# alarm.net
KiCad netlist of a schematic drawn in EAGLE
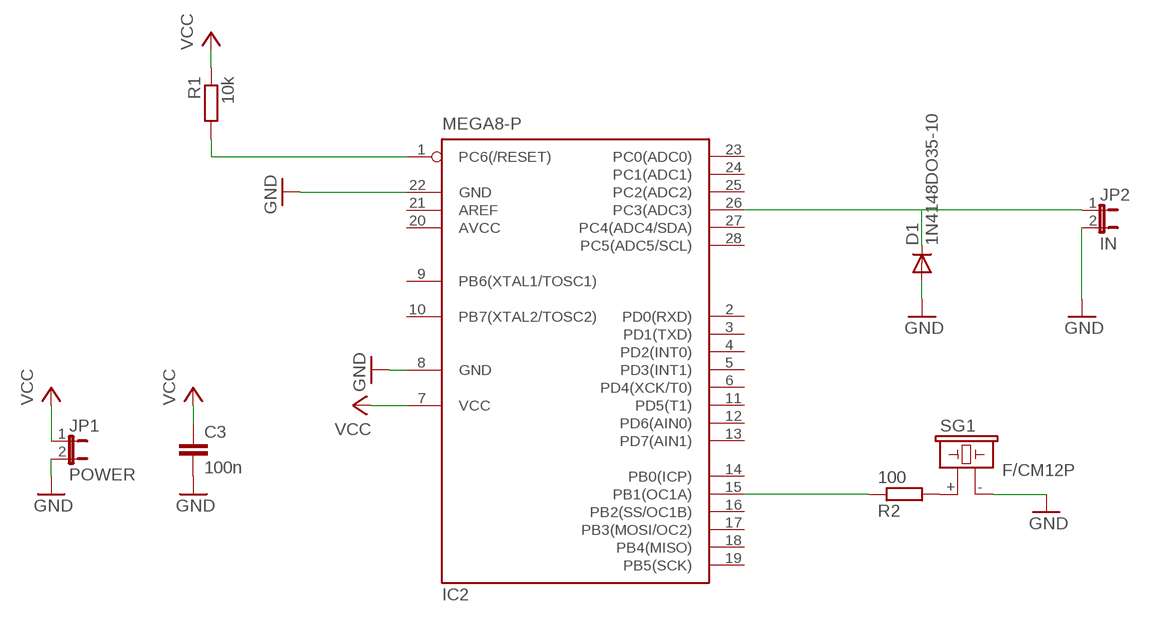
[diagram p0: schematic, sheet 1]

(export (version "E")
  (design (tool "Eeschema 10.0.6"))
  (components
    (comp (ref "C3")
      (value "100n")
      (footprint "eagle-import:C025-024X044")
      (libsource (lib "eagle-import") (part "C-EU025-024X044"))
    )
    (comp (ref "D1")
      (value "1N4148DO35-10")
      (footprint "eagle-import:DO35-10")
      (libsource (lib "eagle-import") (part "1N4148DO35-10"))
    )
    (comp (ref "IC2")
      (value "MEGA8-P")
      (footprint "eagle-import:DIL28-3")
      (libsource (lib "eagle-import") (part "MEGA8-P"))
    )
    (comp (ref "JP1")
      (value "POWER")
      (footprint "eagle-import:JP1")
      (libsource (lib "eagle-import") (part "JP1E"))
    )
    (comp (ref "JP2")
      (value "IN")
      (footprint "eagle-import:JP1")
      (libsource (lib "eagle-import") (part "JP1E"))
    )
    (comp (ref "R1")
      (value "10k")
      (footprint "eagle-import:0207_15")
      (libsource (lib "eagle-import") (part "R-EU_0207/15"))
    )
    (comp (ref "R2")
      (value "100")
      (footprint "eagle-import:0207_10")
      (libsource (lib "eagle-import") (part "R-EU_0207/10"))
    )
    (comp (ref "SG1")
      (value "F/CM12P")
      (footprint "eagle-import:F_CM12P")
      (libsource (lib "eagle-import") (part "F/CM12P"))
    )
  )
  (nets
    (net (code "1") (name "/AVCC") (class "Default")
      (node (ref "IC2") (pin "20") (pinfunction "AVCC_20") (pintype "power_in"))
    )
    (net (code "2") (name "GND") (class "Default")
      (node (ref "C3") (pin "2") (pinfunction "2_2") (pintype "passive"))
      (node (ref "D1") (pin "A") (pinfunction "A_A") (pintype "passive"))
      (node (ref "IC2") (pin "22") (pinfunction "GND_22") (pintype "power_in"))
      (node (ref "IC2") (pin "8") (pinfunction "GND_8") (pintype "power_in"))
      (node (ref "JP1") (pin "2") (pinfunction "2_2") (pintype "passive"))
      (node (ref "JP2") (pin "2") (pinfunction "2_2") (pintype "passive"))
      (node (ref "SG1") (pin "-") (pinfunction "2_-") (pintype "passive"))
    )
    (net (code "3") (name "Net-(IC2-PB1(OC1A))") (class "Default")
      (node (ref "IC2") (pin "15") (pinfunction "PB1(OC1A)_15") (pintype "bidirectional"))
      (node (ref "R2") (pin "1") (pinfunction "1_1") (pintype "passive"))
    )
    (net (code "4") (name "Net-(IC2-PC3(ADC3))") (class "Default")
      (node (ref "D1") (pin "C") (pinfunction "C_C") (pintype "passive"))
      (node (ref "IC2") (pin "26") (pinfunction "PC3(ADC3)_26") (pintype "bidirectional"))
      (node (ref "JP2") (pin "1") (pinfunction "1_1") (pintype "passive"))
    )
    (net (code "5") (name "Net-(IC2-PC6({slash}RESET))") (class "Default")
      (node (ref "IC2") (pin "1") (pinfunction "PC6(/RESET)_1") (pintype "bidirectional"))
      (node (ref "R1") (pin "2") (pinfunction "2_2") (pintype "passive"))
    )
    (net (code "6") (name "Net-(SG1-1)") (class "Default")
      (node (ref "R2") (pin "2") (pinfunction "2_2") (pintype "passive"))
      (node (ref "SG1") (pin "+") (pinfunction "1_+") (pintype "passive"))
    )
    (net (code "7") (name "VCC") (class "Default")
      (node (ref "C3") (pin "1") (pinfunction "1_1") (pintype "passive"))
      (node (ref "IC2") (pin "7") (pinfunction "VCC_7") (pintype "power_in"))
      (node (ref "JP1") (pin "1") (pinfunction "1_1") (pintype "passive"))
      (node (ref "R1") (pin "1") (pinfunction "1_1") (pintype "passive"))
    )
    (net (code "8") (name "unconnected-(IC2-AREF-Pad21)") (class "Default")
      (node (ref "IC2") (pin "21") (pinfunction "AREF_21") (pintype "passive"))
    )
    (net (code "9") (name "unconnected-(IC2-PB0(ICP)-Pad14)") (class "Default")
      (node (ref "IC2") (pin "14") (pinfunction "PB0(ICP)_14") (pintype "bidirectional"))
    )
    (net (code "10") (name "unconnected-(IC2-PB2(SS{slash}OC1B)-Pad16)") (class "Default")
      (node (ref "IC2") (pin "16") (pinfunction "PB2(SS/OC1B)_16") (pintype "bidirectional"))
    )
    (net (code "11") (name "unconnected-(IC2-PB3(MOSI{slash}OC2)-Pad17)") (class "Default")
      (node (ref "IC2") (pin "17") (pinfunction "PB3(MOSI/OC2)_17") (pintype "bidirectional"))
    )
    (net (code "12") (name "unconnected-(IC2-PB4(MISO)-Pad18)") (class "Default")
      (node (ref "IC2") (pin "18") (pinfunction "PB4(MISO)_18") (pintype "bidirectional"))
    )
    (net (code "13") (name "unconnected-(IC2-PB5(SCK)-Pad19)") (class "Default")
      (node (ref "IC2") (pin "19") (pinfunction "PB5(SCK)_19") (pintype "bidirectional"))
    )
    (net (code "14") (name "unconnected-(IC2-PB6(XTAL1{slash}TOSC1)-Pad9)") (class "Default")
      (node (ref "IC2") (pin "9") (pinfunction "PB6(XTAL1/TOSC1)_9") (pintype "bidirectional"))
    )
    (net (code "15") (name "unconnected-(IC2-PB7(XTAL2{slash}TOSC2)-Pad10)") (class "Default")
      (node (ref "IC2") (pin "10") (pinfunction "PB7(XTAL2/TOSC2)_10") (pintype "bidirectional"))
    )
    (net (code "16") (name "unconnected-(IC2-PC0(ADC0)-Pad23)") (class "Default")
      (node (ref "IC2") (pin "23") (pinfunction "PC0(ADC0)_23") (pintype "bidirectional"))
    )
    (net (code "17") (name "unconnected-(IC2-PC1(ADC1)-Pad24)") (class "Default")
      (node (ref "IC2") (pin "24") (pinfunction "PC1(ADC1)_24") (pintype "bidirectional"))
    )
    (net (code "18") (name "unconnected-(IC2-PC2(ADC2)-Pad25)") (class "Default")
      (node (ref "IC2") (pin "25") (pinfunction "PC2(ADC2)_25") (pintype "bidirectional"))
    )
    (net (code "19") (name "unconnected-(IC2-PC4(ADC4{slash}SDA)-Pad27)") (class "Default")
      (node (ref "IC2") (pin "27") (pinfunction "PC4(ADC4/SDA)_27") (pintype "bidirectional"))
    )
    (net (code "20") (name "unconnected-(IC2-PC5(ADC5{slash}SCL)-Pad28)") (class "Default")
      (node (ref "IC2") (pin "28") (pinfunction "PC5(ADC5/SCL)_28") (pintype "bidirectional"))
    )
    (net (code "21") (name "unconnected-(IC2-PD0(RXD)-Pad2)") (class "Default")
      (node (ref "IC2") (pin "2") (pinfunction "PD0(RXD)_2") (pintype "bidirectional"))
    )
    (net (code "22") (name "unconnected-(IC2-PD1(TXD)-Pad3)") (class "Default")
      (node (ref "IC2") (pin "3") (pinfunction "PD1(TXD)_3") (pintype "bidirectional"))
    )
    (net (code "23") (name "unconnected-(IC2-PD2(INT0)-Pad4)") (class "Default")
      (node (ref "IC2") (pin "4") (pinfunction "PD2(INT0)_4") (pintype "bidirectional"))
    )
    (net (code "24") (name "unconnected-(IC2-PD3(INT1)-Pad5)") (class "Default")
      (node (ref "IC2") (pin "5") (pinfunction "PD3(INT1)_5") (pintype "bidirectional"))
    )
    (net (code "25") (name "unconnected-(IC2-PD4(XCK{slash}T0)-Pad6)") (class "Default")
      (node (ref "IC2") (pin "6") (pinfunction "PD4(XCK/T0)_6") (pintype "bidirectional"))
    )
    (net (code "26") (name "unconnected-(IC2-PD5(T1)-Pad11)") (class "Default")
      (node (ref "IC2") (pin "11") (pinfunction "PD5(T1)_11") (pintype "bidirectional"))
    )
    (net (code "27") (name "unconnected-(IC2-PD6(AIN0)-Pad12)") (class "Default")
      (node (ref "IC2") (pin "12") (pinfunction "PD6(AIN0)_12") (pintype "bidirectional"))
    )
    (net (code "28") (name "unconnected-(IC2-PD7(AIN1)-Pad13)") (class "Default")
      (node (ref "IC2") (pin "13") (pinfunction "PD7(AIN1)_13") (pintype "bidirectional"))
    )
  )
)
